# Input_stages.net
KiCad netlist of a schematic drawn in Altium Designer
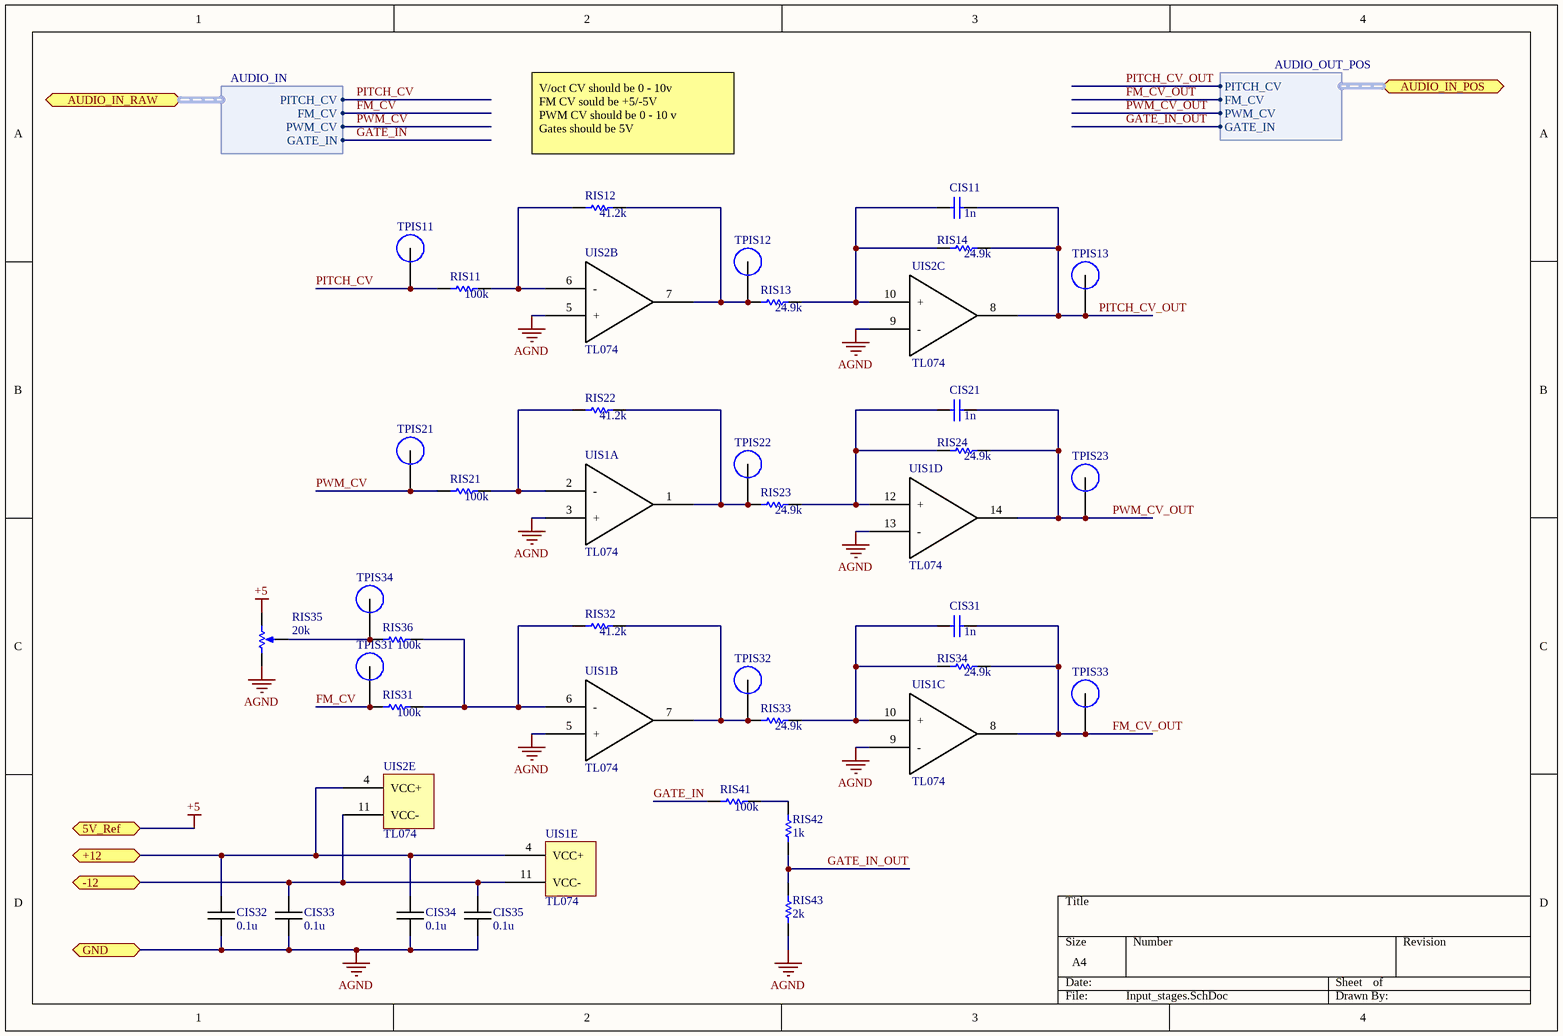
[diagram p0: Input_stages.SchDoc]

(export (version "E")
  (design (tool "Eeschema 10.0.6"))
  (components
    (comp (ref "CIS11")
      (value "1n")
      (footprint "C 0603 / 1608")
      (description "Capacitor")
      (fields (field (name "Comment") "Cap") (field (name "PUBLISHER") "Altium Limited"))
      (libsource (lib "Standard") (part "Cap"))
    )
    (comp (ref "CIS21")
      (value "1n")
      (footprint "C 0603 / 1608")
      (description "Capacitor")
      (fields (field (name "Comment") "Cap") (field (name "PUBLISHER") "Altium Limited"))
      (libsource (lib "Standard") (part "Cap"))
    )
    (comp (ref "CIS31")
      (value "1n")
      (footprint "C 0603 / 1608")
      (description "Capacitor")
      (fields (field (name "Comment") "Cap") (field (name "PUBLISHER") "Altium Limited"))
      (libsource (lib "Standard") (part "Cap"))
    )
    (comp (ref "CIS32")
      (value "0.1u")
      (footprint "C 0603 / 1608")
      (libsource (lib "Standard") (part "Capacitor"))
    )
    (comp (ref "CIS33")
      (value "0.1u")
      (footprint "C 0603 / 1608")
      (libsource (lib "Standard") (part "Capacitor"))
    )
    (comp (ref "CIS34")
      (value "0.1u")
      (footprint "C 0603 / 1608")
      (libsource (lib "Standard") (part "Capacitor"))
    )
    (comp (ref "CIS35")
      (value "0.1u")
      (footprint "C 0603 / 1608")
      (libsource (lib "Standard") (part "Capacitor"))
    )
    (comp (ref "RIS11")
      (value "100k")
      (footprint "RES0603R")
      (description "Resistor")
      (fields (field (name "Comment") "Res1") (field (name "PUBLISHER") "Altium Limited"))
      (libsource (lib "Standard") (part "Res1"))
    )
    (comp (ref "RIS12")
      (value "41.2k")
      (footprint "RES0603R")
      (description "Resistor")
      (fields (field (name "Comment") "Res1") (field (name "PUBLISHER") "Altium Limited"))
      (libsource (lib "Standard") (part "Res1"))
    )
    (comp (ref "RIS13")
      (value "24.9k")
      (footprint "RES0603R")
      (description "Resistor")
      (fields (field (name "Comment") "Res1") (field (name "PUBLISHER") "Altium Limited"))
      (libsource (lib "Standard") (part "Res1"))
    )
    (comp (ref "RIS14")
      (value "24.9k")
      (footprint "RES0603R")
      (description "Resistor")
      (fields (field (name "Comment") "Res1") (field (name "PUBLISHER") "Altium Limited"))
      (libsource (lib "Standard") (part "Res1"))
    )
    (comp (ref "RIS21")
      (value "100k")
      (footprint "RES0603R")
      (description "Resistor")
      (fields (field (name "Comment") "Res1") (field (name "PUBLISHER") "Altium Limited"))
      (libsource (lib "Standard") (part "Res1"))
    )
    (comp (ref "RIS22")
      (value "41.2k")
      (footprint "RES0603R")
      (description "Resistor")
      (fields (field (name "Comment") "Res1") (field (name "PUBLISHER") "Altium Limited"))
      (libsource (lib "Standard") (part "Res1"))
    )
    (comp (ref "RIS23")
      (value "24.9k")
      (footprint "RES0603R")
      (description "Resistor")
      (fields (field (name "Comment") "Res1") (field (name "PUBLISHER") "Altium Limited"))
      (libsource (lib "Standard") (part "Res1"))
    )
    (comp (ref "RIS24")
      (value "24.9k")
      (footprint "RES0603R")
      (description "Resistor")
      (fields (field (name "Comment") "Res1") (field (name "PUBLISHER") "Altium Limited"))
      (libsource (lib "Standard") (part "Res1"))
    )
    (comp (ref "RIS31")
      (value "100k")
      (footprint "RES0603R")
      (description "Resistor")
      (fields (field (name "Comment") "Res1") (field (name "PUBLISHER") "Altium Limited"))
      (libsource (lib "Standard") (part "Res1"))
    )
    (comp (ref "RIS32")
      (value "41.2k")
      (footprint "RES0603R")
      (description "Resistor")
      (fields (field (name "Comment") "Res1") (field (name "PUBLISHER") "Altium Limited"))
      (libsource (lib "Standard") (part "Res1"))
    )
    (comp (ref "RIS33")
      (value "24.9k")
      (footprint "RES0603R")
      (description "Resistor")
      (fields (field (name "Comment") "Res1") (field (name "PUBLISHER") "Altium Limited"))
      (libsource (lib "Standard") (part "Res1"))
    )
    (comp (ref "RIS34")
      (value "24.9k")
      (footprint "RES0603R")
      (description "Resistor")
      (fields (field (name "Comment") "Res1") (field (name "PUBLISHER") "Altium Limited"))
      (libsource (lib "Standard") (part "Res1"))
    )
    (comp (ref "RIS35")
      (value "20k")
      (footprint "SMD_POT_3x3mm")
      (description "Potentiometer")
      (fields (field (name "PUBLISHER") "Altium Limited"))
      (libsource (lib "Standard") (part "RPot"))
    )
    (comp (ref "RIS36")
      (value "100k")
      (footprint "RES0603R")
      (description "Resistor")
      (fields (field (name "Comment") "Res1") (field (name "PUBLISHER") "Altium Limited"))
      (libsource (lib "Standard") (part "Res1"))
    )
    (comp (ref "RIS41")
      (value "100k")
      (footprint "RES0603R")
      (description "Resistor")
      (fields (field (name "Comment") "Res1") (field (name "PUBLISHER") "Altium Limited"))
      (libsource (lib "Standard") (part "Res1"))
    )
    (comp (ref "RIS42")
      (value "1k")
      (footprint "RES0603R")
      (description "Resistor")
      (fields (field (name "Comment") "Res1") (field (name "PUBLISHER") "Altium Limited"))
      (libsource (lib "Standard") (part "Res1"))
    )
    (comp (ref "RIS43")
      (value "2k")
      (footprint "RES0603R")
      (description "Resistor")
      (fields (field (name "Comment") "Res1") (field (name "PUBLISHER") "Altium Limited"))
      (libsource (lib "Standard") (part "Res1"))
    )
    (comp (ref "TPIS11")
      (value "Test Point")
      (footprint "Test POint")
      (libsource (lib "Standard") (part "Test Point"))
    )
    (comp (ref "TPIS12")
      (value "Test Point")
      (footprint "Test POint")
      (libsource (lib "Standard") (part "Test Point"))
    )
    (comp (ref "TPIS13")
      (value "Test Point")
      (footprint "Test POint")
      (libsource (lib "Standard") (part "Test Point"))
    )
    (comp (ref "TPIS21")
      (value "Test Point")
      (footprint "Test POint")
      (libsource (lib "Standard") (part "Test Point"))
    )
    (comp (ref "TPIS22")
      (value "Test Point")
      (footprint "Test POint")
      (libsource (lib "Standard") (part "Test Point"))
    )
    (comp (ref "TPIS23")
      (value "Test Point")
      (footprint "Test POint")
      (libsource (lib "Standard") (part "Test Point"))
    )
    (comp (ref "TPIS31")
      (value "Test Point")
      (footprint "Test POint")
      (libsource (lib "Standard") (part "Test Point"))
    )
    (comp (ref "TPIS32")
      (value "Test Point")
      (footprint "Test POint")
      (libsource (lib "Standard") (part "Test Point"))
    )
    (comp (ref "TPIS33")
      (value "Test Point")
      (footprint "Test POint")
      (libsource (lib "Standard") (part "Test Point"))
    )
    (comp (ref "TPIS34")
      (value "Test Point")
      (footprint "Test POint")
      (libsource (lib "Standard") (part "Test Point"))
    )
    (comp (ref "UIS1") (value "TL074") (footprint "SOIC-14") (libsource (lib "") (part "TL074_1")))
    (comp (ref "UIS2") (value "TL074") (footprint "SOIC-14") (libsource (lib "IC") (part "TL074")))
  )
  (nets
    (net (code "3") (name "+5") (class "Default")
      (node (ref "RIS35") (pin "2") (pinfunction "BOT_2") (pintype "passive"))
    )
    (net (code "4") (name "/+12") (class "Default")
      (node (ref "CIS32") (pin "2") (pinfunction "1_2") (pintype "passive"))
      (node (ref "CIS34") (pin "2") (pinfunction "1_2") (pintype "passive"))
      (node (ref "UIS1") (pin "4") (pinfunction "VCC+_4") (pintype "passive"))
      (node (ref "UIS2") (pin "4") (pinfunction "VCC+_4") (pintype "passive"))
    )
    (net (code "5") (name "/-12") (class "Default")
      (node (ref "CIS33") (pin "2") (pinfunction "1_2") (pintype "passive"))
      (node (ref "CIS35") (pin "2") (pinfunction "1_2") (pintype "passive"))
      (node (ref "UIS1") (pin "11") (pinfunction "VCC-_11") (pintype "passive"))
      (node (ref "UIS2") (pin "11") (pinfunction "VCC-_11") (pintype "passive"))
    )
    (net (code "6") (name "/FM_CV") (class "Default")
      (node (ref "RIS31") (pin "1") (pinfunction "1_1") (pintype "passive"))
      (node (ref "TPIS31") (pin "1") (pintype "passive"))
    )
    (net (code "7") (name "/FM_CV_OUT") (class "Default")
      (node (ref "CIS31") (pin "2") (pinfunction "2_2") (pintype "passive"))
      (node (ref "RIS34") (pin "2") (pinfunction "2_2") (pintype "passive"))
      (node (ref "TPIS33") (pin "1") (pintype "passive"))
      (node (ref "UIS1") (pin "8") (pinfunction "OUT_8") (pintype "passive"))
    )
    (net (code "8") (name "/GATE_IN") (class "Default")
      (node (ref "RIS41") (pin "1") (pinfunction "1_1") (pintype "passive"))
    )
    (net (code "9") (name "/GATE_IN_OUT") (class "Default")
      (node (ref "RIS42") (pin "1") (pinfunction "1_1") (pintype "passive"))
      (node (ref "RIS43") (pin "2") (pinfunction "2_2") (pintype "passive"))
    )
    (net (code "10") (name "/PITCH_CV") (class "Default")
      (node (ref "RIS11") (pin "1") (pinfunction "1_1") (pintype "passive"))
      (node (ref "TPIS11") (pin "1") (pintype "passive"))
    )
    (net (code "11") (name "/PITCH_CV_OUT") (class "Default")
      (node (ref "CIS11") (pin "2") (pinfunction "2_2") (pintype "passive"))
      (node (ref "RIS14") (pin "2") (pinfunction "2_2") (pintype "passive"))
      (node (ref "TPIS13") (pin "1") (pintype "passive"))
      (node (ref "UIS2") (pin "8") (pinfunction "OUT_8") (pintype "passive"))
    )
    (net (code "12") (name "/PWM_CV") (class "Default")
      (node (ref "RIS21") (pin "1") (pinfunction "1_1") (pintype "passive"))
      (node (ref "TPIS21") (pin "1") (pintype "passive"))
    )
    (net (code "13") (name "/PWM_CV_OUT") (class "Default")
      (node (ref "CIS21") (pin "2") (pinfunction "2_2") (pintype "passive"))
      (node (ref "RIS24") (pin "2") (pinfunction "2_2") (pintype "passive"))
      (node (ref "TPIS23") (pin "1") (pintype "passive"))
      (node (ref "UIS1") (pin "14") (pinfunction "OUT_14") (pintype "passive"))
    )
    (net (code "16") (name "AGND") (class "Default")
      (node (ref "CIS32") (pin "1") (pinfunction "1_1") (pintype "passive"))
      (node (ref "CIS33") (pin "1") (pinfunction "1_1") (pintype "passive"))
      (node (ref "CIS34") (pin "1") (pinfunction "1_1") (pintype "passive"))
      (node (ref "CIS35") (pin "1") (pinfunction "1_1") (pintype "passive"))
      (node (ref "RIS35") (pin "1") (pinfunction "TOP_1") (pintype "passive"))
      (node (ref "RIS43") (pin "1") (pinfunction "1_1") (pintype "passive"))
      (node (ref "UIS1") (pin "13") (pinfunction "-_13") (pintype "passive"))
      (node (ref "UIS1") (pin "3") (pinfunction "+_3") (pintype "passive"))
      (node (ref "UIS1") (pin "5") (pinfunction "+_5") (pintype "passive"))
      (node (ref "UIS1") (pin "9") (pinfunction "-_9") (pintype "passive"))
      (node (ref "UIS2") (pin "5") (pinfunction "+_5") (pintype "passive"))
      (node (ref "UIS2") (pin "9") (pinfunction "-_9") (pintype "passive"))
    )
    (net (code "17") (name "Net-(RIS35-TAP)") (class "Default")
      (node (ref "RIS35") (pin "3") (pinfunction "TAP_3") (pintype "passive"))
      (node (ref "RIS36") (pin "1") (pinfunction "1_1") (pintype "passive"))
      (node (ref "TPIS34") (pin "1") (pintype "passive"))
    )
    (net (code "18") (name "Net-(RIS41-Pad2)") (class "Default")
      (node (ref "RIS41") (pin "2") (pinfunction "2_2") (pintype "passive"))
      (node (ref "RIS42") (pin "2") (pinfunction "2_2") (pintype "passive"))
    )
    (net (code "19") (name "Net-(UIS1A--)") (class "Default")
      (node (ref "RIS21") (pin "2") (pinfunction "2_2") (pintype "passive"))
      (node (ref "RIS22") (pin "1") (pinfunction "1_1") (pintype "passive"))
      (node (ref "UIS1") (pin "2") (pinfunction "-_2") (pintype "passive"))
    )
    (net (code "20") (name "Net-(UIS1A-OUT)") (class "Default")
      (node (ref "RIS22") (pin "2") (pinfunction "2_2") (pintype "passive"))
      (node (ref "RIS23") (pin "1") (pinfunction "1_1") (pintype "passive"))
      (node (ref "TPIS22") (pin "1") (pintype "passive"))
      (node (ref "UIS1") (pin "1") (pinfunction "OUT_1") (pintype "passive"))
    )
    (net (code "21") (name "Net-(UIS1B--)") (class "Default")
      (node (ref "RIS31") (pin "2") (pinfunction "2_2") (pintype "passive"))
      (node (ref "RIS32") (pin "1") (pinfunction "1_1") (pintype "passive"))
      (node (ref "RIS36") (pin "2") (pinfunction "2_2") (pintype "passive"))
      (node (ref "UIS1") (pin "6") (pinfunction "-_6") (pintype "passive"))
    )
    (net (code "22") (name "Net-(UIS1B-OUT)") (class "Default")
      (node (ref "RIS32") (pin "2") (pinfunction "2_2") (pintype "passive"))
      (node (ref "RIS33") (pin "1") (pinfunction "1_1") (pintype "passive"))
      (node (ref "TPIS32") (pin "1") (pintype "passive"))
      (node (ref "UIS1") (pin "7") (pinfunction "OUT_7") (pintype "passive"))
    )
    (net (code "23") (name "Net-(UIS1C-+)") (class "Default")
      (node (ref "CIS31") (pin "1") (pinfunction "1_1") (pintype "passive"))
      (node (ref "RIS33") (pin "2") (pinfunction "2_2") (pintype "passive"))
      (node (ref "RIS34") (pin "1") (pinfunction "1_1") (pintype "passive"))
      (node (ref "UIS1") (pin "10") (pinfunction "+_10") (pintype "passive"))
    )
    (net (code "24") (name "Net-(UIS1D-+)") (class "Default")
      (node (ref "CIS21") (pin "1") (pinfunction "1_1") (pintype "passive"))
      (node (ref "RIS23") (pin "2") (pinfunction "2_2") (pintype "passive"))
      (node (ref "RIS24") (pin "1") (pinfunction "1_1") (pintype "passive"))
      (node (ref "UIS1") (pin "12") (pinfunction "+_12") (pintype "passive"))
    )
    (net (code "25") (name "Net-(UIS2B--)") (class "Default")
      (node (ref "RIS11") (pin "2") (pinfunction "2_2") (pintype "passive"))
      (node (ref "RIS12") (pin "1") (pinfunction "1_1") (pintype "passive"))
      (node (ref "UIS2") (pin "6") (pinfunction "-_6") (pintype "passive"))
    )
    (net (code "26") (name "Net-(UIS2B-OUT)") (class "Default")
      (node (ref "RIS12") (pin "2") (pinfunction "2_2") (pintype "passive"))
      (node (ref "RIS13") (pin "1") (pinfunction "1_1") (pintype "passive"))
      (node (ref "TPIS12") (pin "1") (pintype "passive"))
      (node (ref "UIS2") (pin "7") (pinfunction "OUT_7") (pintype "passive"))
    )
    (net (code "27") (name "Net-(UIS2C-+)") (class "Default")
      (node (ref "CIS11") (pin "1") (pinfunction "1_1") (pintype "passive"))
      (node (ref "RIS13") (pin "2") (pinfunction "2_2") (pintype "passive"))
      (node (ref "RIS14") (pin "1") (pinfunction "1_1") (pintype "passive"))
      (node (ref "UIS2") (pin "10") (pinfunction "+_10") (pintype "passive"))
    )
  )
)
